# Soldeerbout_P4.net
KiCad netlist of a schematic drawn in Altium Designer
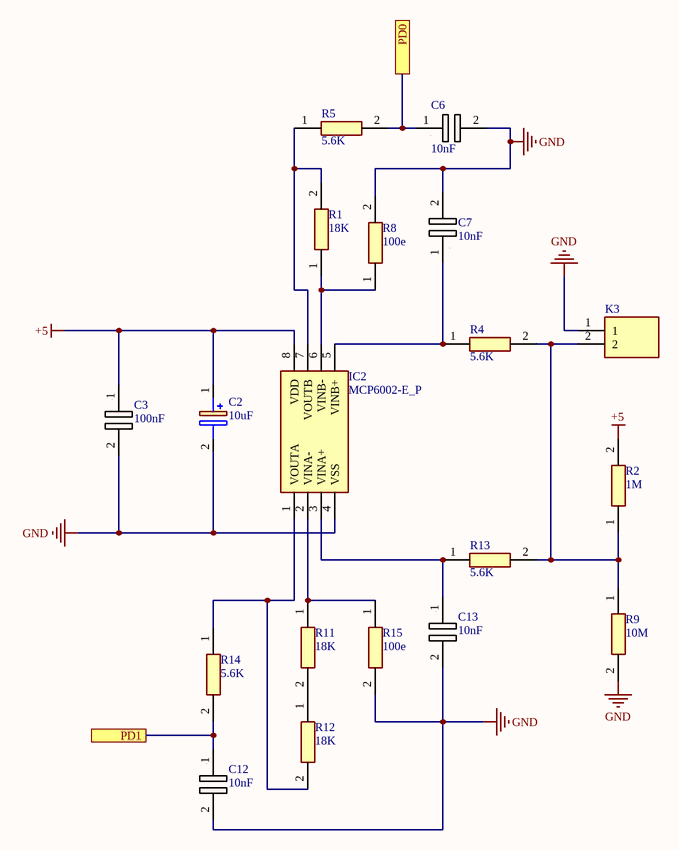
[diagram p0: Soldeerbout_P4.SchDoc]

(export (version "E")
  (design (tool "Eeschema 10.0.6"))
  (components
    (comp (ref "C2")
      (value "10uF")
      (footprint "SamacSys:C 50V 10µF")
      (description "Capacitor Polarised")
      (fields (field (name "MANUFACTURER_PART_NUMBER") "ESS106M050AE2AA"))
      (libsource (lib "SamacSys") (part "ESS106M050AE2AA"))
    )
    (comp (ref "C3")
      (value "100nF")
      (footprint "SamacSys:0805")
      (description "Resistor")
      (fields (field (name "MANUFACTURER_PART_NUMBER") "ESR10EZPJ183"))
      (libsource (lib "SamacSys") (part "ESR10EZPJ183_1"))
    )
    (comp (ref "C6")
      (value "10nF")
      (footprint "SamacSys:0805")
      (description "Resistor")
      (fields (field (name "MANUFACTURER_PART_NUMBER") "ESR10EZPJ183"))
      (libsource (lib "SamacSys") (part "ESR10EZPJ183_1"))
    )
    (comp (ref "C7")
      (value "10nF")
      (footprint "SamacSys:0805")
      (description "Resistor")
      (fields (field (name "MANUFACTURER_PART_NUMBER") "ESR10EZPJ183"))
      (libsource (lib "SamacSys") (part "ESR10EZPJ183_1"))
    )
    (comp (ref "C12")
      (value "10nF")
      (footprint "SamacSys:0805")
      (description "Resistor")
      (fields (field (name "MANUFACTURER_PART_NUMBER") "ESR10EZPJ183"))
      (libsource (lib "SamacSys") (part "ESR10EZPJ183_1"))
    )
    (comp (ref "C13")
      (value "10nF")
      (footprint "SamacSys:0805")
      (description "Resistor")
      (fields (field (name "MANUFACTURER_PART_NUMBER") "ESR10EZPJ183"))
      (libsource (lib "SamacSys") (part "ESR10EZPJ183_1"))
    )
    (comp (ref "IC2")
      (value "MCP6002-E_P")
      (footprint "SamacSys:IC2 dual opamp")
      (description "Integrated Circuit")
      (fields
        (field (name "MOUSER2 PART NUMBER") "579-MCP6002-E/P")
        (field (name "MANUFACTURER_PART_NUMBER") "MCP6002-E/P")
      )
      (libsource (lib "SamacSys") (part "MCP6002-E_P"))
    )
    (comp (ref "K3")
      (value "TB007-508-02BE")
      (footprint "SamacSys:K printkroonsteen 5.08")
      (description "Connector")
      (fields (field (name "MOUSER2 PART NUMBER") "490-TB007-508-02BE"))
      (libsource (lib "SamacSys") (part "TB007-508-02BE"))
    )
    (comp (ref "R1")
      (value "18K")
      (footprint "SamacSys:0805")
      (description "Resistor")
      (fields (field (name "MANUFACTURER_PART_NUMBER") "ESR10EZPJ183"))
      (libsource (lib "") (part "ESR10EZPJ183_2"))
    )
    (comp (ref "R2")
      (value "1M")
      (footprint "SamacSys:0805")
      (description "Resistor")
      (fields (field (name "MANUFACTURER_PART_NUMBER") "ESR10EZPJ183"))
      (libsource (lib "") (part "ESR10EZPJ183_2"))
    )
    (comp (ref "R4")
      (value "5.6K")
      (footprint "SamacSys:0805")
      (description "Resistor")
      (fields (field (name "MANUFACTURER_PART_NUMBER") "ESR10EZPJ183"))
      (libsource (lib "") (part "ESR10EZPJ183_1"))
    )
    (comp (ref "R5")
      (value "5.6K")
      (footprint "SamacSys:0805")
      (description "Resistor")
      (fields (field (name "MANUFACTURER_PART_NUMBER") "ESR10EZPJ183"))
      (libsource (lib "") (part "ESR10EZPJ183_1"))
    )
    (comp (ref "R8")
      (value "100e")
      (footprint "SamacSys:0805")
      (description "Resistor")
      (fields (field (name "MANUFACTURER_PART_NUMBER") "ESR10EZPJ183"))
      (libsource (lib "") (part "ESR10EZPJ183_2"))
    )
    (comp (ref "R9")
      (value "10M")
      (footprint "SamacSys:0805")
      (description "Resistor")
      (fields (field (name "MANUFACTURER_PART_NUMBER") "ESR10EZPJ183"))
      (libsource (lib "SamacSys") (part "ESR10EZPJ183"))
    )
    (comp (ref "R11")
      (value "18K")
      (footprint "SamacSys:0805")
      (description "Resistor")
      (fields (field (name "MANUFACTURER_PART_NUMBER") "ESR10EZPJ183"))
      (libsource (lib "SamacSys") (part "ESR10EZPJ183"))
    )
    (comp (ref "R12")
      (value "18K")
      (footprint "SamacSys:0805")
      (description "Resistor")
      (fields (field (name "MANUFACTURER_PART_NUMBER") "ESR10EZPJ183"))
      (libsource (lib "SamacSys") (part "ESR10EZPJ183"))
    )
    (comp (ref "R13")
      (value "5.6K")
      (footprint "SamacSys:0805")
      (description "Resistor")
      (fields (field (name "MANUFACTURER_PART_NUMBER") "ESR10EZPJ183"))
      (libsource (lib "") (part "ESR10EZPJ183_1"))
    )
    (comp (ref "R14")
      (value "5.6K")
      (footprint "SamacSys:0805")
      (description "Resistor")
      (fields (field (name "MANUFACTURER_PART_NUMBER") "ESR10EZPJ183"))
      (libsource (lib "SamacSys") (part "ESR10EZPJ183"))
    )
    (comp (ref "R15")
      (value "100e")
      (footprint "SamacSys:0805")
      (description "Resistor")
      (fields (field (name "MANUFACTURER_PART_NUMBER") "ESR10EZPJ183"))
      (libsource (lib "SamacSys") (part "ESR10EZPJ183"))
    )
  )
  (nets
    (net (code "1") (name "+5") (class "Default")
      (node (ref "C2") (pin "1") (pinfunction "+_1") (pintype "passive"))
      (node (ref "C3") (pin "1") (pinfunction "1_1") (pintype "passive"))
      (node (ref "IC2") (pin "8") (pinfunction "VDD_8") (pintype "passive"))
      (node (ref "R2") (pin "2") (pinfunction "2_2") (pintype "passive"))
    )
    (net (code "2") (name "/PD0") (class "Default")
      (node (ref "C6") (pin "1") (pinfunction "1_1") (pintype "passive"))
      (node (ref "R5") (pin "2") (pinfunction "2_2") (pintype "passive"))
    )
    (net (code "3") (name "/PD1") (class "Default")
      (node (ref "C12") (pin "1") (pinfunction "1_1") (pintype "passive"))
      (node (ref "R14") (pin "2") (pinfunction "2_2") (pintype "passive"))
    )
    (net (code "4") (name "GND") (class "Default")
      (node (ref "C12") (pin "2") (pinfunction "2_2") (pintype "passive"))
      (node (ref "C13") (pin "2") (pinfunction "2_2") (pintype "passive"))
      (node (ref "C2") (pin "2") (pinfunction "-_2") (pintype "passive"))
      (node (ref "C3") (pin "2") (pinfunction "2_2") (pintype "passive"))
      (node (ref "C6") (pin "2") (pinfunction "2_2") (pintype "passive"))
      (node (ref "C7") (pin "2") (pinfunction "2_2") (pintype "passive"))
      (node (ref "IC2") (pin "4") (pinfunction "VSS_4") (pintype "passive"))
      (node (ref "K3") (pin "1") (pinfunction "1_1") (pintype "passive"))
      (node (ref "R15") (pin "2") (pinfunction "2_2") (pintype "passive"))
      (node (ref "R8") (pin "2") (pinfunction "2_2") (pintype "passive"))
      (node (ref "R9") (pin "2") (pinfunction "2_2") (pintype "passive"))
    )
    (net (code "5") (name "Net-(IC2-VINA+)") (class "Default")
      (node (ref "C13") (pin "1") (pinfunction "1_1") (pintype "passive"))
      (node (ref "IC2") (pin "3") (pinfunction "VINA+_3") (pintype "passive"))
      (node (ref "R13") (pin "1") (pinfunction "1_1") (pintype "passive"))
    )
    (net (code "6") (name "Net-(IC2-VINA-)") (class "Default")
      (node (ref "IC2") (pin "2") (pinfunction "VINA-_2") (pintype "passive"))
      (node (ref "R11") (pin "1") (pinfunction "1_1") (pintype "passive"))
      (node (ref "R15") (pin "1") (pinfunction "1_1") (pintype "passive"))
    )
    (net (code "7") (name "Net-(IC2-VINB+)") (class "Default")
      (node (ref "C7") (pin "1") (pinfunction "1_1") (pintype "passive"))
      (node (ref "IC2") (pin "5") (pinfunction "VINB+_5") (pintype "passive"))
      (node (ref "R4") (pin "1") (pinfunction "1_1") (pintype "passive"))
    )
    (net (code "8") (name "Net-(IC2-VINB-)") (class "Default")
      (node (ref "IC2") (pin "6") (pinfunction "VINB-_6") (pintype "passive"))
      (node (ref "R1") (pin "1") (pinfunction "1_1") (pintype "passive"))
      (node (ref "R8") (pin "1") (pinfunction "1_1") (pintype "passive"))
    )
    (net (code "9") (name "Net-(IC2-VOUTA)") (class "Default")
      (node (ref "IC2") (pin "1") (pinfunction "VOUTA_1") (pintype "passive"))
      (node (ref "R12") (pin "2") (pinfunction "2_2") (pintype "passive"))
      (node (ref "R14") (pin "1") (pinfunction "1_1") (pintype "passive"))
    )
    (net (code "10") (name "Net-(IC2-VOUTB)") (class "Default")
      (node (ref "IC2") (pin "7") (pinfunction "VOUTB_7") (pintype "passive"))
      (node (ref "R1") (pin "2") (pinfunction "2_2") (pintype "passive"))
      (node (ref "R5") (pin "1") (pinfunction "1_1") (pintype "passive"))
    )
    (net (code "11") (name "Net-(K3-Pad2)") (class "Default")
      (node (ref "K3") (pin "2") (pinfunction "2_2") (pintype "passive"))
      (node (ref "R13") (pin "2") (pinfunction "2_2") (pintype "passive"))
      (node (ref "R2") (pin "1") (pinfunction "1_1") (pintype "passive"))
      (node (ref "R4") (pin "2") (pinfunction "2_2") (pintype "passive"))
      (node (ref "R9") (pin "1") (pinfunction "1_1") (pintype "passive"))
    )
    (net (code "12") (name "Net-(R11-Pad2)") (class "Default")
      (node (ref "R11") (pin "2") (pinfunction "2_2") (pintype "passive"))
      (node (ref "R12") (pin "1") (pinfunction "1_1") (pintype "passive"))
    )
  )
)
